# EC544_v1.net
KiCad netlist of a schematic drawn in EAGLE
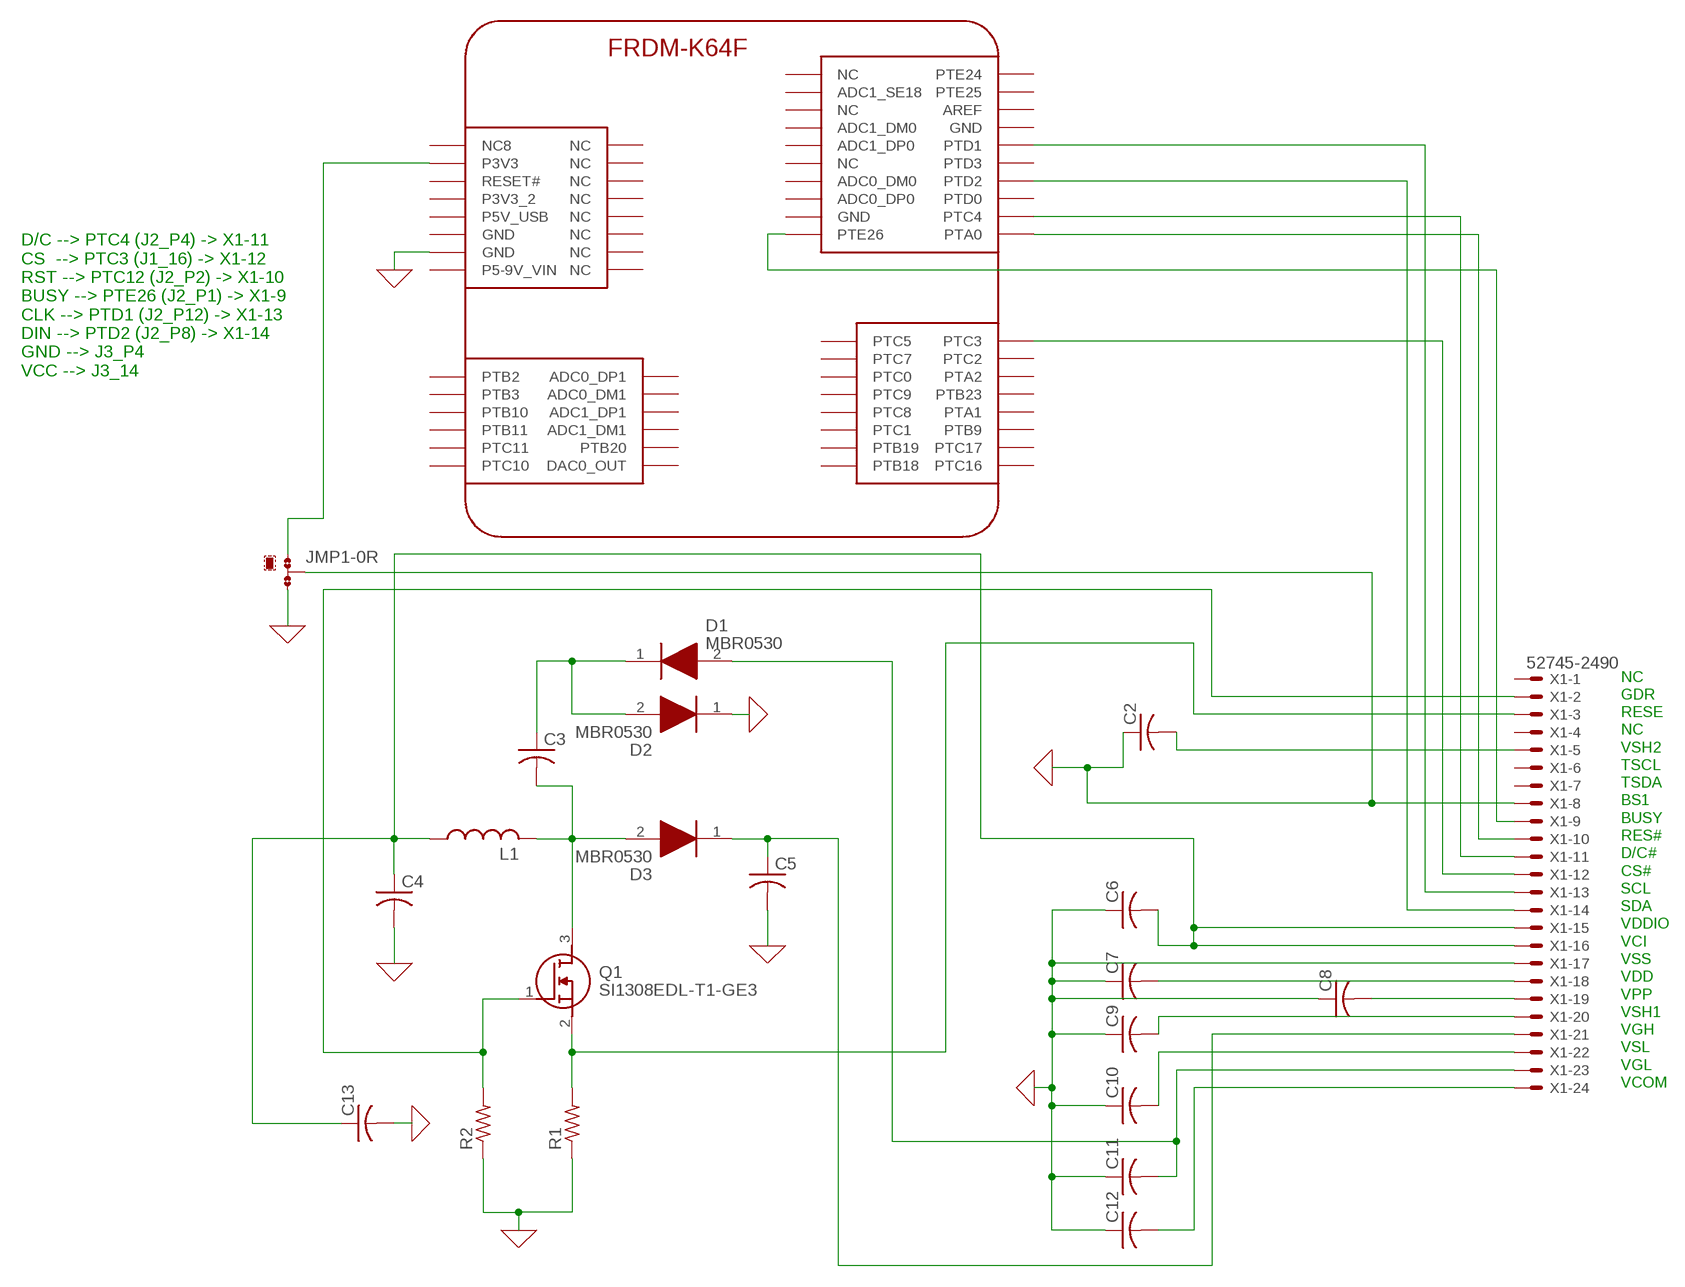
[diagram p0: schematic, sheet 1]

(export (version "E")
  (design (tool "Eeschema 10.0.6"))
  (components
    (comp (ref "C2")
      (value "C-US025-024X044")
      (footprint "eagle-import:C025-024X044")
      (libsource (lib "eagle-import") (part "C-US025-024X044"))
    )
    (comp (ref "C3")
      (value "C-US025-024X044")
      (footprint "eagle-import:C025-024X044")
      (libsource (lib "eagle-import") (part "C-US025-024X044"))
    )
    (comp (ref "C4")
      (value "C-US025-024X044")
      (footprint "eagle-import:C025-024X044")
      (libsource (lib "eagle-import") (part "C-US025-024X044"))
    )
    (comp (ref "C5")
      (value "C-US025-024X044")
      (footprint "eagle-import:C025-024X044")
      (libsource (lib "eagle-import") (part "C-US025-024X044"))
    )
    (comp (ref "C6")
      (value "C-US025-024X044")
      (footprint "eagle-import:C025-024X044")
      (libsource (lib "eagle-import") (part "C-US025-024X044"))
    )
    (comp (ref "C7")
      (value "C-US025-024X044")
      (footprint "eagle-import:C025-024X044")
      (libsource (lib "eagle-import") (part "C-US025-024X044"))
    )
    (comp (ref "C8")
      (value "C-US025-024X044")
      (footprint "eagle-import:C025-024X044")
      (libsource (lib "eagle-import") (part "C-US025-024X044"))
    )
    (comp (ref "C9")
      (value "C-US025-024X044")
      (footprint "eagle-import:C025-024X044")
      (libsource (lib "eagle-import") (part "C-US025-024X044"))
    )
    (comp (ref "C10")
      (value "C-US025-024X044")
      (footprint "eagle-import:C025-024X044")
      (libsource (lib "eagle-import") (part "C-US025-024X044"))
    )
    (comp (ref "C11")
      (value "C-US025-024X044")
      (footprint "eagle-import:C025-024X044")
      (libsource (lib "eagle-import") (part "C-US025-024X044"))
    )
    (comp (ref "C12")
      (value "C-US025-024X044")
      (footprint "eagle-import:C025-024X044")
      (libsource (lib "eagle-import") (part "C-US025-024X044"))
    )
    (comp (ref "C13")
      (value "C-US025-024X044")
      (footprint "eagle-import:C025-024X044")
      (libsource (lib "eagle-import") (part "C-US025-024X044"))
    )
    (comp (ref "D1")
      (value "MBR0530")
      (footprint "eagle-import:SOD3716X135N")
      (fields (field (name "MOUSER_PART_NUMBER") "512-MBR0530"))
      (libsource (lib "eagle-import") (part "MBR0530"))
    )
    (comp (ref "D2")
      (value "MBR0530")
      (footprint "eagle-import:SOD3716X135N")
      (fields (field (name "MOUSER_PART_NUMBER") "512-MBR0530"))
      (libsource (lib "eagle-import") (part "MBR0530"))
    )
    (comp (ref "D3")
      (value "MBR0530")
      (footprint "eagle-import:SOD3716X135N")
      (fields (field (name "MOUSER_PART_NUMBER") "512-MBR0530"))
      (libsource (lib "eagle-import") (part "MBR0530"))
    )
    (comp (ref "FRDM1")
      (value "FRDM-K64FNORMAL")
      (footprint "eagle-import:FRDM_K64F")
      (libsource (lib "eagle-import") (part "FRDM-K64FNORMAL"))
    )
    (comp (ref "JMP1")
      (value "0R-JUMPA")
      (footprint "eagle-import:A0R-JMP")
      (libsource (lib "eagle-import") (part "0R-JUMPA"))
    )
    (comp (ref "L1")
      (value "L-USPIS2816")
      (footprint "eagle-import:PIS2816")
      (libsource (lib "eagle-import") (part "L-USPIS2816"))
    )
    (comp (ref "Q1")
      (value "SI1308EDL-T1-GE3")
      (footprint "eagle-import:SOT65P210X110-3N")
      (fields
        (field (name "MANUFACTURER_PART_NUMBER") "Si1308EDL-T1-GE3")
        (field (name "MOUSER_PART_NUMBER") "78-SI1308EDL-T1-GE3")
      )
      (libsource (lib "eagle-import") (part "SI1308EDL-T1-GE3"))
    )
    (comp (ref "R1")
      (value "R-US_0204/5")
      (footprint "eagle-import:0204_5")
      (libsource (lib "eagle-import") (part "R-US_0204/5"))
    )
    (comp (ref "R2")
      (value "R-US_0204/5")
      (footprint "eagle-import:0204_5")
      (libsource (lib "eagle-import") (part "R-US_0204/5"))
    )
    (comp (ref "X1")
      (value "52745-2490")
      (footprint "eagle-import:52745-2490")
      (fields (field (name "MF") "MOLEX"))
      (libsource (lib "eagle-import") (part "52745-2490"))
    )
  )
  (nets
    (net (code "1") (name "GND") (class "Default")
      (node (ref "C10") (pin "1") (pinfunction "1_1") (pintype "passive"))
      (node (ref "C11") (pin "1") (pinfunction "1_1") (pintype "passive"))
      (node (ref "C12") (pin "1") (pinfunction "1_1") (pintype "passive"))
      (node (ref "C13") (pin "2") (pinfunction "2_2") (pintype "passive"))
      (node (ref "C2") (pin "1") (pinfunction "1_1") (pintype "passive"))
      (node (ref "C4") (pin "2") (pinfunction "2_2") (pintype "passive"))
      (node (ref "C5") (pin "2") (pinfunction "2_2") (pintype "passive"))
      (node (ref "C6") (pin "1") (pinfunction "1_1") (pintype "passive"))
      (node (ref "C7") (pin "1") (pinfunction "1_1") (pintype "passive"))
      (node (ref "C8") (pin "1") (pinfunction "1_1") (pintype "passive"))
      (node (ref "C9") (pin "1") (pinfunction "1_1") (pintype "passive"))
      (node (ref "D2") (pin "1") (pinfunction "K_1") (pintype "bidirectional"))
      (node (ref "FRDM1") (pin "J3.14") (pinfunction "GND_J3.14") (pintype "bidirectional"))
      (node (ref "JMP1") (pin "2") (pinfunction "2_2") (pintype "passive"))
      (node (ref "JMP1") (pin "3") (pinfunction "3_3") (pintype "passive"))
      (node (ref "R1") (pin "1") (pinfunction "1_1") (pintype "passive"))
      (node (ref "R2") (pin "1") (pinfunction "1_1") (pintype "passive"))
      (node (ref "X1") (pin "17") (pinfunction "S_17") (pintype "passive"))
      (node (ref "X1") (pin "8") (pinfunction "S_8") (pintype "passive"))
    )
    (net (code "2") (name "Net-(D1-A)") (class "Default")
      (node (ref "C11") (pin "2") (pinfunction "2_2") (pintype "passive"))
      (node (ref "D1") (pin "2") (pinfunction "A_2") (pintype "bidirectional"))
      (node (ref "X1") (pin "23") (pinfunction "S_23") (pintype "passive"))
    )
    (net (code "3") (name "Net-(D1-K)") (class "Default")
      (node (ref "C3") (pin "1") (pinfunction "1_1") (pintype "passive"))
      (node (ref "D1") (pin "1") (pinfunction "K_1") (pintype "bidirectional"))
      (node (ref "D2") (pin "2") (pinfunction "A_2") (pintype "bidirectional"))
    )
    (net (code "4") (name "Net-(D3-A)") (class "Default")
      (node (ref "C3") (pin "2") (pinfunction "2_2") (pintype "passive"))
      (node (ref "D3") (pin "2") (pinfunction "A_2") (pintype "bidirectional"))
      (node (ref "L1") (pin "2") (pinfunction "2_2") (pintype "passive"))
      (node (ref "Q1") (pin "3") (pinfunction "D_3") (pintype "bidirectional"))
    )
    (net (code "5") (name "Net-(D3-K)") (class "Default")
      (node (ref "C5") (pin "1") (pinfunction "1_1") (pintype "passive"))
      (node (ref "D3") (pin "1") (pinfunction "K_1") (pintype "bidirectional"))
      (node (ref "X1") (pin "21") (pinfunction "S_21") (pintype "passive"))
    )
    (net (code "6") (name "Net-(FRDM1-P3V3)") (class "Default")
      (node (ref "FRDM1") (pin "J3.4") (pinfunction "P3V3_J3.4") (pintype "bidirectional"))
      (node (ref "JMP1") (pin "1") (pinfunction "1_1") (pintype "passive"))
    )
    (net (code "7") (name "Net-(FRDM1-PTA0)") (class "Default")
      (node (ref "FRDM1") (pin "J2.2") (pinfunction "PTA0_J2.2") (pintype "bidirectional"))
      (node (ref "X1") (pin "10") (pinfunction "S_10") (pintype "passive"))
    )
    (net (code "8") (name "Net-(FRDM1-PTC3)") (class "Default")
      (node (ref "FRDM1") (pin "J1.16") (pinfunction "PTC3_J1.16") (pintype "bidirectional"))
      (node (ref "X1") (pin "12") (pinfunction "S_12") (pintype "passive"))
    )
    (net (code "9") (name "Net-(FRDM1-PTC4)") (class "Default")
      (node (ref "FRDM1") (pin "J2.4") (pinfunction "PTC4_J2.4") (pintype "bidirectional"))
      (node (ref "X1") (pin "11") (pinfunction "S_11") (pintype "passive"))
    )
    (net (code "10") (name "Net-(FRDM1-PTD1)") (class "Default")
      (node (ref "FRDM1") (pin "J2.12") (pinfunction "PTD1_J2.12") (pintype "bidirectional"))
      (node (ref "X1") (pin "13") (pinfunction "S_13") (pintype "passive"))
    )
    (net (code "11") (name "Net-(FRDM1-PTD2)") (class "Default")
      (node (ref "FRDM1") (pin "J2.8") (pinfunction "PTD2_J2.8") (pintype "bidirectional"))
      (node (ref "X1") (pin "14") (pinfunction "S_14") (pintype "passive"))
    )
    (net (code "12") (name "Net-(FRDM1-PTE26)") (class "Default")
      (node (ref "FRDM1") (pin "J2.1") (pinfunction "PTE26_J2.1") (pintype "bidirectional"))
      (node (ref "X1") (pin "9") (pinfunction "S_9") (pintype "passive"))
    )
    (net (code "13") (name "Net-(Q1-G)") (class "Default")
      (node (ref "Q1") (pin "1") (pinfunction "G_1") (pintype "bidirectional"))
      (node (ref "R2") (pin "2") (pinfunction "2_2") (pintype "passive"))
      (node (ref "X1") (pin "2") (pinfunction "S_2") (pintype "passive"))
    )
    (net (code "14") (name "Net-(Q1-S)") (class "Default")
      (node (ref "Q1") (pin "2") (pinfunction "S_2") (pintype "bidirectional"))
      (node (ref "R1") (pin "2") (pinfunction "2_2") (pintype "passive"))
      (node (ref "X1") (pin "3") (pinfunction "S_3") (pintype "passive"))
    )
    (net (code "15") (name "Net-(X1G-S)") (class "Default")
      (node (ref "C13") (pin "1") (pinfunction "1_1") (pintype "passive"))
      (node (ref "C4") (pin "1") (pinfunction "1_1") (pintype "passive"))
      (node (ref "C6") (pin "2") (pinfunction "2_2") (pintype "passive"))
      (node (ref "L1") (pin "1") (pinfunction "1_1") (pintype "passive"))
      (node (ref "X1") (pin "15") (pinfunction "S_15") (pintype "passive"))
      (node (ref "X1") (pin "16") (pinfunction "S_16") (pintype "passive"))
    )
    (net (code "16") (name "Net-(X1J-S)") (class "Default")
      (node (ref "C7") (pin "2") (pinfunction "2_2") (pintype "passive"))
      (node (ref "X1") (pin "18") (pinfunction "S_18") (pintype "passive"))
    )
    (net (code "17") (name "Net-(X1K-S)") (class "Default")
      (node (ref "C8") (pin "2") (pinfunction "2_2") (pintype "passive"))
      (node (ref "X1") (pin "19") (pinfunction "S_19") (pintype "passive"))
    )
    (net (code "18") (name "Net-(X1M-S)") (class "Default")
      (node (ref "C9") (pin "2") (pinfunction "2_2") (pintype "passive"))
      (node (ref "X1") (pin "20") (pinfunction "S_20") (pintype "passive"))
    )
    (net (code "19") (name "Net-(X1O-S)") (class "Default")
      (node (ref "C10") (pin "2") (pinfunction "2_2") (pintype "passive"))
      (node (ref "X1") (pin "22") (pinfunction "S_22") (pintype "passive"))
    )
    (net (code "20") (name "Net-(X1Q-S)") (class "Default")
      (node (ref "C12") (pin "2") (pinfunction "2_2") (pintype "passive"))
      (node (ref "X1") (pin "24") (pinfunction "S_24") (pintype "passive"))
    )
    (net (code "21") (name "Net-(X1T-S)") (class "Default")
      (node (ref "C2") (pin "2") (pinfunction "2_2") (pintype "passive"))
      (node (ref "X1") (pin "5") (pinfunction "S_5") (pintype "passive"))
    )
    (net (code "22") (name "unconnected-(FRDM1-ADC0_DM0-PadJ2.7)") (class "Default")
      (node (ref "FRDM1") (pin "J2.7") (pinfunction "ADC0_DM0_J2.7") (pintype "bidirectional"))
    )
    (net (code "23") (name "unconnected-(FRDM1-ADC0_DM1-PadJ4.3)") (class "Default")
      (node (ref "FRDM1") (pin "J4.3") (pinfunction "ADC0_DM1_J4.3") (pintype "bidirectional"))
    )
    (net (code "24") (name "unconnected-(FRDM1-ADC0_DP0-PadJ2.5)") (class "Default")
      (node (ref "FRDM1") (pin "J2.5") (pinfunction "ADC0_DP0_J2.5") (pintype "bidirectional"))
    )
    (net (code "25") (name "unconnected-(FRDM1-ADC0_DP1-PadJ4.1)") (class "Default")
      (node (ref "FRDM1") (pin "J4.1") (pinfunction "ADC0_DP1_J4.1") (pintype "bidirectional"))
    )
    (net (code "26") (name "unconnected-(FRDM1-ADC1_DM0-PadJ2.13)") (class "Default")
      (node (ref "FRDM1") (pin "J2.13") (pinfunction "ADC1_DM0_J2.13") (pintype "bidirectional"))
    )
    (net (code "27") (name "unconnected-(FRDM1-ADC1_DM1-PadJ4.7)") (class "Default")
      (node (ref "FRDM1") (pin "J4.7") (pinfunction "ADC1_DM1_J4.7") (pintype "bidirectional"))
    )
    (net (code "28") (name "unconnected-(FRDM1-ADC1_DP0-PadJ2.11)") (class "Default")
      (node (ref "FRDM1") (pin "J2.11") (pinfunction "ADC1_DP0_J2.11") (pintype "bidirectional"))
    )
    (net (code "29") (name "unconnected-(FRDM1-ADC1_DP1-PadJ4.5)") (class "Default")
      (node (ref "FRDM1") (pin "J4.5") (pinfunction "ADC1_DP1_J4.5") (pintype "bidirectional"))
    )
    (net (code "30") (name "unconnected-(FRDM1-ADC1_SE18-PadJ2.17)") (class "Default")
      (node (ref "FRDM1") (pin "J2.17") (pinfunction "ADC1_SE18_J2.17") (pintype "bidirectional"))
    )
    (net (code "31") (name "unconnected-(FRDM1-AREF-PadJ2.16)") (class "Default")
      (node (ref "FRDM1") (pin "J2.16") (pinfunction "AREF_J2.16") (pintype "bidirectional"))
    )
    (net (code "32") (name "unconnected-(FRDM1-DAC0_OUT-PadJ4.11)") (class "Default")
      (node (ref "FRDM1") (pin "J4.11") (pinfunction "DAC0_OUT_J4.11") (pintype "bidirectional"))
    )
    (net (code "33") (name "unconnected-(FRDM1-GND-PadJ2.3)") (class "Default")
      (node (ref "FRDM1") (pin "J2.3") (pinfunction "GND_J2.3") (pintype "bidirectional"))
    )
    (net (code "34") (name "unconnected-(FRDM1-GND-PadJ2.14)") (class "Default")
      (node (ref "FRDM1") (pin "J2.14") (pinfunction "GND_J2.14") (pintype "bidirectional"))
    )
    (net (code "35") (name "unconnected-(FRDM1-GND-PadJ3.12)") (class "Default")
      (node (ref "FRDM1") (pin "J3.12") (pinfunction "GND_J3.12") (pintype "bidirectional"))
    )
    (net (code "36") (name "unconnected-(FRDM1-NC-PadJ2.9)") (class "Default")
      (node (ref "FRDM1") (pin "J2.9") (pinfunction "NC_J2.9") (pintype "bidirectional"))
    )
    (net (code "37") (name "unconnected-(FRDM1-NC-PadJ2.15)") (class "Default")
      (node (ref "FRDM1") (pin "J2.15") (pinfunction "NC_J2.15") (pintype "bidirectional"))
    )
    (net (code "38") (name "unconnected-(FRDM1-NC-PadJ2.19)") (class "Default")
      (node (ref "FRDM1") (pin "J2.19") (pinfunction "NC_J2.19") (pintype "bidirectional"))
    )
    (net (code "39") (name "unconnected-(FRDM1-NC-PadJ3.1)") (class "Default")
      (node (ref "FRDM1") (pin "J3.1") (pinfunction "NC_J3.1") (pintype "bidirectional"))
    )
    (net (code "40") (name "unconnected-(FRDM1-NC-PadJ3.2)") (class "Default")
      (node (ref "FRDM1") (pin "J3.2") (pinfunction "NC_J3.2") (pintype "bidirectional"))
    )
    (net (code "41") (name "unconnected-(FRDM1-NC-PadJ3.3)") (class "Default")
      (node (ref "FRDM1") (pin "J3.3") (pinfunction "NC_J3.3") (pintype "bidirectional"))
    )
    (net (code "42") (name "unconnected-(FRDM1-NC-PadJ3.5)") (class "Default")
      (node (ref "FRDM1") (pin "J3.5") (pinfunction "NC_J3.5") (pintype "bidirectional"))
    )
    (net (code "43") (name "unconnected-(FRDM1-NC-PadJ3.7)") (class "Default")
      (node (ref "FRDM1") (pin "J3.7") (pinfunction "NC_J3.7") (pintype "bidirectional"))
    )
    (net (code "44") (name "unconnected-(FRDM1-NC-PadJ3.9)") (class "Default")
      (node (ref "FRDM1") (pin "J3.9") (pinfunction "NC_J3.9") (pintype "bidirectional"))
    )
    (net (code "45") (name "unconnected-(FRDM1-NC-PadJ3.11)") (class "Default")
      (node (ref "FRDM1") (pin "J3.11") (pinfunction "NC_J3.11") (pintype "bidirectional"))
    )
    (net (code "46") (name "unconnected-(FRDM1-NC-PadJ3.13)") (class "Default")
      (node (ref "FRDM1") (pin "J3.13") (pinfunction "NC_J3.13") (pintype "bidirectional"))
    )
    (net (code "47") (name "unconnected-(FRDM1-NC8-PadJ3.15)") (class "Default")
      (node (ref "FRDM1") (pin "J3.15") (pinfunction "NC8_J3.15") (pintype "bidirectional"))
    )
    (net (code "48") (name "unconnected-(FRDM1-P3V3_2-PadJ3.8)") (class "Default")
      (node (ref "FRDM1") (pin "J3.8") (pinfunction "P3V3_2_J3.8") (pintype "bidirectional"))
    )
    (net (code "49") (name "unconnected-(FRDM1-P5-9V_VIN-PadJ3.16)") (class "Default")
      (node (ref "FRDM1") (pin "J3.16") (pinfunction "P5-9V_VIN_J3.16") (pintype "bidirectional"))
    )
    (net (code "50") (name "unconnected-(FRDM1-P5V_USB-PadJ3.10)") (class "Default")
      (node (ref "FRDM1") (pin "J3.10") (pinfunction "P5V_USB_J3.10") (pintype "bidirectional"))
    )
    (net (code "51") (name "unconnected-(FRDM1-PTA1-PadJ1.8)") (class "Default")
      (node (ref "FRDM1") (pin "J1.8") (pinfunction "PTA1_J1.8") (pintype "bidirectional"))
    )
    (net (code "52") (name "unconnected-(FRDM1-PTA2-PadJ1.12)") (class "Default")
      (node (ref "FRDM1") (pin "J1.12") (pinfunction "PTA2_J1.12") (pintype "bidirectional"))
    )
    (net (code "53") (name "unconnected-(FRDM1-PTB2-PadJ4.2)") (class "Default")
      (node (ref "FRDM1") (pin "J4.2") (pinfunction "PTB2_J4.2") (pintype "bidirectional"))
    )
    (net (code "54") (name "unconnected-(FRDM1-PTB3-PadJ4.4)") (class "Default")
      (node (ref "FRDM1") (pin "J4.4") (pinfunction "PTB3_J4.4") (pintype "bidirectional"))
    )
    (net (code "55") (name "unconnected-(FRDM1-PTB9-PadJ1.6)") (class "Default")
      (node (ref "FRDM1") (pin "J1.6") (pinfunction "PTB9_J1.6") (pintype "bidirectional"))
    )
    (net (code "56") (name "unconnected-(FRDM1-PTB10-PadJ4.6)") (class "Default")
      (node (ref "FRDM1") (pin "J4.6") (pinfunction "PTB10_J4.6") (pintype "bidirectional"))
    )
    (net (code "57") (name "unconnected-(FRDM1-PTB11-PadJ4.8)") (class "Default")
      (node (ref "FRDM1") (pin "J4.8") (pinfunction "PTB11_J4.8") (pintype "bidirectional"))
    )
    (net (code "58") (name "unconnected-(FRDM1-PTB18-PadJ1.1)") (class "Default")
      (node (ref "FRDM1") (pin "J1.1") (pinfunction "PTB18_J1.1") (pintype "bidirectional"))
    )
    (net (code "59") (name "unconnected-(FRDM1-PTB19-PadJ1.3)") (class "Default")
      (node (ref "FRDM1") (pin "J1.3") (pinfunction "PTB19_J1.3") (pintype "bidirectional"))
    )
    (net (code "60") (name "unconnected-(FRDM1-PTB20-PadJ4.9)") (class "Default")
      (node (ref "FRDM1") (pin "J4.9") (pinfunction "PTB20_J4.9") (pintype "bidirectional"))
    )
    (net (code "61") (name "unconnected-(FRDM1-PTB23-PadJ1.10)") (class "Default")
      (node (ref "FRDM1") (pin "J1.10") (pinfunction "PTB23_J1.10") (pintype "bidirectional"))
    )
    (net (code "62") (name "unconnected-(FRDM1-PTC0-PadJ1.11)") (class "Default")
      (node (ref "FRDM1") (pin "J1.11") (pinfunction "PTC0_J1.11") (pintype "bidirectional"))
    )
    (net (code "63") (name "unconnected-(FRDM1-PTC1-PadJ1.5)") (class "Default")
      (node (ref "FRDM1") (pin "J1.5") (pinfunction "PTC1_J1.5") (pintype "bidirectional"))
    )
    (net (code "64") (name "unconnected-(FRDM1-PTC2-PadJ1.14)") (class "Default")
      (node (ref "FRDM1") (pin "J1.14") (pinfunction "PTC2_J1.14") (pintype "bidirectional"))
    )
    (net (code "65") (name "unconnected-(FRDM1-PTC5-PadJ1.15)") (class "Default")
      (node (ref "FRDM1") (pin "J1.15") (pinfunction "PTC5_J1.15") (pintype "bidirectional"))
    )
    (net (code "66") (name "unconnected-(FRDM1-PTC7-PadJ1.13)") (class "Default")
      (node (ref "FRDM1") (pin "J1.13") (pinfunction "PTC7_J1.13") (pintype "bidirectional"))
    )
    (net (code "67") (name "unconnected-(FRDM1-PTC8-PadJ1.7)") (class "Default")
      (node (ref "FRDM1") (pin "J1.7") (pinfunction "PTC8_J1.7") (pintype "bidirectional"))
    )
    (net (code "68") (name "unconnected-(FRDM1-PTC9-PadJ1.9)") (class "Default")
      (node (ref "FRDM1") (pin "J1.9") (pinfunction "PTC9_J1.9") (pintype "bidirectional"))
    )
    (net (code "69") (name "unconnected-(FRDM1-PTC10-PadJ4.12)") (class "Default")
      (node (ref "FRDM1") (pin "J4.12") (pinfunction "PTC10_J4.12") (pintype "bidirectional"))
    )
    (net (code "70") (name "unconnected-(FRDM1-PTC11-PadJ4.10)") (class "Default")
      (node (ref "FRDM1") (pin "J4.10") (pinfunction "PTC11_J4.10") (pintype "bidirectional"))
    )
    (net (code "71") (name "unconnected-(FRDM1-PTC16-PadJ1.2)") (class "Default")
      (node (ref "FRDM1") (pin "J1.2") (pinfunction "PTC16_J1.2") (pintype "bidirectional"))
    )
    (net (code "72") (name "unconnected-(FRDM1-PTC17-PadJ1.4)") (class "Default")
      (node (ref "FRDM1") (pin "J1.4") (pinfunction "PTC17_J1.4") (pintype "bidirectional"))
    )
    (net (code "73") (name "unconnected-(FRDM1-PTD0-PadJ2.6)") (class "Default")
      (node (ref "FRDM1") (pin "J2.6") (pinfunction "PTD0_J2.6") (pintype "bidirectional"))
    )
    (net (code "74") (name "unconnected-(FRDM1-PTD3-PadJ2.10)") (class "Default")
      (node (ref "FRDM1") (pin "J2.10") (pinfunction "PTD3_J2.10") (pintype "bidirectional"))
    )
    (net (code "75") (name "unconnected-(FRDM1-PTE24-PadJ2.20)") (class "Default")
      (node (ref "FRDM1") (pin "J2.20") (pinfunction "PTE24_J2.20") (pintype "bidirectional"))
    )
    (net (code "76") (name "unconnected-(FRDM1-PTE25-PadJ2.18)") (class "Default")
      (node (ref "FRDM1") (pin "J2.18") (pinfunction "PTE25_J2.18") (pintype "bidirectional"))
    )
    (net (code "77") (name "unconnected-(FRDM1-RESET#-PadJ3.6)") (class "Default")
      (node (ref "FRDM1") (pin "J3.6") (pinfunction "RESET#_J3.6") (pintype "bidirectional"))
    )
    (net (code "78") (name "unconnected-(X1A-S-Pad1)") (class "Default")
      (node (ref "X1") (pin "1") (pinfunction "S_1") (pintype "passive"))
    )
    (net (code "79") (name "unconnected-(X1S-S-Pad4)") (class "Default")
      (node (ref "X1") (pin "4") (pinfunction "S_4") (pintype "passive"))
    )
    (net (code "80") (name "unconnected-(X1U-S-Pad6)") (class "Default")
      (node (ref "X1") (pin "6") (pinfunction "S_6") (pintype "passive"))
    )
    (net (code "81") (name "unconnected-(X1V-S-Pad7)") (class "Default")
      (node (ref "X1") (pin "7") (pinfunction "S_7") (pintype "passive"))
    )
  )
)
